# observer.net
KiCad netlist of a schematic drawn in EAGLE
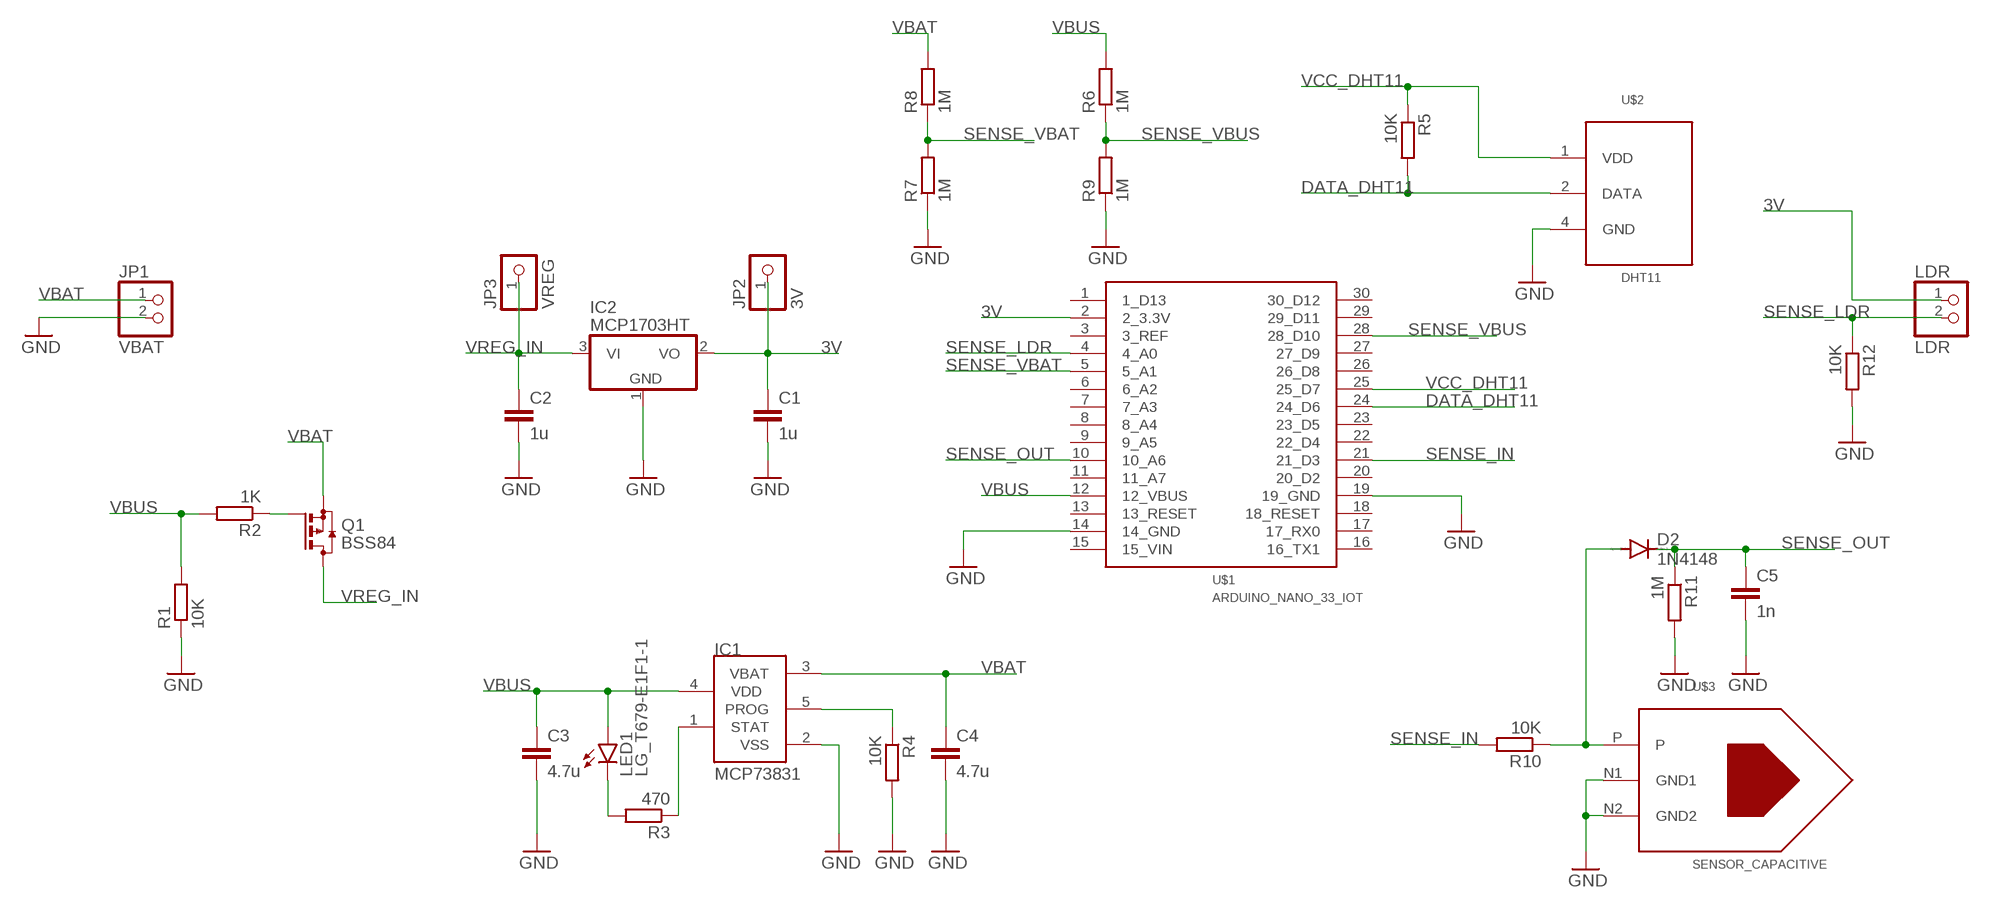
[diagram p0: schematic, sheet 1]

(export (version "E")
  (design (tool "Eeschema 10.0.6"))
  (components
    (comp (ref "C1")
      (value "1u")
      (footprint "eagle-import:C0805")
      (libsource (lib "eagle-import") (part "C-EUC0805"))
    )
    (comp (ref "C2")
      (value "1u")
      (footprint "eagle-import:C0805")
      (libsource (lib "eagle-import") (part "C-EUC0805"))
    )
    (comp (ref "C3")
      (value "4.7u")
      (footprint "eagle-import:C0805")
      (libsource (lib "eagle-import") (part "C-EUC0805"))
    )
    (comp (ref "C4")
      (value "4.7u")
      (footprint "eagle-import:C0805")
      (libsource (lib "eagle-import") (part "C-EUC0805"))
    )
    (comp (ref "C5")
      (value "1n")
      (footprint "eagle-import:C0805")
      (libsource (lib "eagle-import") (part "C-EUC0805"))
    )
    (comp (ref "D2")
      (value "1N4148")
      (footprint "eagle-import:MICROMELF-W")
      (libsource (lib "eagle-import") (part "DIODE-MICROMELF-W"))
    )
    (comp (ref "IC1")
      (value "MCP73831")
      (footprint "eagle-import:SOT23-5L")
      (libsource (lib "eagle-import") (part "MCP73831"))
    )
    (comp (ref "IC2")
      (value "MCP1703HT")
      (footprint "eagle-import:SOT23")
      (libsource (lib "eagle-import") (part "MCP1703CB"))
    )
    (comp (ref "JP1")
      (value "VBAT")
      (footprint "eagle-import:1X02")
      (libsource (lib "eagle-import") (part "PINHD-1X2"))
    )
    (comp (ref "JP2")
      (value "3V")
      (footprint "eagle-import:1X01")
      (libsource (lib "eagle-import") (part "PINHD-1X1"))
    )
    (comp (ref "JP3")
      (value "VREG")
      (footprint "eagle-import:1X01")
      (libsource (lib "eagle-import") (part "PINHD-1X1"))
    )
    (comp (ref "LDR")
      (value "LDR")
      (footprint "eagle-import:1X02")
      (libsource (lib "eagle-import") (part "PINHD-1X2"))
    )
    (comp (ref "LED1")
      (value "LG_T679-E1F1-1")
      (footprint "eagle-import:PLCC2")
      (libsource (lib "eagle-import") (part "_T679-?-1E1F1LG"))
    )
    (comp (ref "Q1")
      (value "BSS84")
      (footprint "eagle-import:SOT23")
      (libsource (lib "eagle-import") (part "BSS84"))
    )
    (comp (ref "R1")
      (value "10K")
      (footprint "eagle-import:R0805")
      (libsource (lib "eagle-import") (part "R-EU_R0805"))
    )
    (comp (ref "R2")
      (value "1K")
      (footprint "eagle-import:R0805")
      (libsource (lib "eagle-import") (part "R-EU_R0805"))
    )
    (comp (ref "R3")
      (value "470")
      (footprint "eagle-import:R0805")
      (libsource (lib "eagle-import") (part "R-EU_R0805"))
    )
    (comp (ref "R4")
      (value "10K")
      (footprint "eagle-import:R0805")
      (libsource (lib "eagle-import") (part "R-EU_R0805"))
    )
    (comp (ref "R5")
      (value "10K")
      (footprint "eagle-import:R0805")
      (libsource (lib "eagle-import") (part "R-EU_R0805"))
    )
    (comp (ref "R6")
      (value "1M")
      (footprint "eagle-import:R0805")
      (libsource (lib "eagle-import") (part "R-EU_R0805"))
    )
    (comp (ref "R7")
      (value "1M")
      (footprint "eagle-import:R0805")
      (libsource (lib "eagle-import") (part "R-EU_R0805"))
    )
    (comp (ref "R8")
      (value "1M")
      (footprint "eagle-import:R0805")
      (libsource (lib "eagle-import") (part "R-EU_R0805"))
    )
    (comp (ref "R9")
      (value "1M")
      (footprint "eagle-import:R0805")
      (libsource (lib "eagle-import") (part "R-EU_R0805"))
    )
    (comp (ref "R10")
      (value "10K")
      (footprint "eagle-import:R0805")
      (libsource (lib "eagle-import") (part "R-EU_R0805"))
    )
    (comp (ref "R11")
      (value "1M")
      (footprint "eagle-import:R0805")
      (libsource (lib "eagle-import") (part "R-EU_R0805"))
    )
    (comp (ref "R12")
      (value "10K")
      (footprint "eagle-import:R0805")
      (libsource (lib "eagle-import") (part "R-EU_R0805"))
    )
    (comp (ref "U$1")
      (value "ARDUINO_NANO_33_IOT")
      (footprint "eagle-import:ARDUINO_NANO_33_IOT")
      (libsource (lib "eagle-import") (part "ARDUINO_NANO_33_IOT"))
    )
    (comp (ref "U$2")
      (value "DHT11")
      (footprint "eagle-import:DHT11")
      (libsource (lib "eagle-import") (part "DHT11"))
    )
    (comp (ref "U$3")
      (value "SENSOR_CAPACITIVE")
      (footprint "eagle-import:SENSOR_CAPACITIVE_MOISTURE")
      (libsource (lib "eagle-import") (part "SENSOR_CAPACITIVE"))
    )
  )
  (nets
    (net (code "1") (name "/3V") (class "Default")
      (node (ref "C1") (pin "1") (pinfunction "1_1") (pintype "passive"))
      (node (ref "IC2") (pin "2") (pinfunction "VO_2") (pintype "passive"))
      (node (ref "JP2") (pin "1") (pinfunction "1_1") (pintype "passive"))
      (node (ref "LDR") (pin "1") (pinfunction "1_1") (pintype "passive"))
      (node (ref "U$1") (pin "2") (pinfunction "2_3.3V_2") (pintype "bidirectional"))
    )
    (net (code "2") (name "/DATA_DHT11") (class "Default")
      (node (ref "R5") (pin "2") (pinfunction "2_2") (pintype "passive"))
      (node (ref "U$1") (pin "24") (pinfunction "24_D6_24") (pintype "bidirectional"))
      (node (ref "U$2") (pin "2") (pinfunction "DATA_2") (pintype "bidirectional"))
    )
    (net (code "3") (name "/SENSE_IN") (class "Default")
      (node (ref "R10") (pin "2") (pinfunction "2_2") (pintype "passive"))
      (node (ref "U$1") (pin "21") (pinfunction "21_D3_21") (pintype "bidirectional"))
    )
    (net (code "4") (name "/SENSE_LDR") (class "Default")
      (node (ref "LDR") (pin "2") (pinfunction "2_2") (pintype "passive"))
      (node (ref "R12") (pin "1") (pinfunction "1_1") (pintype "passive"))
      (node (ref "U$1") (pin "4") (pinfunction "4_A0_4") (pintype "bidirectional"))
    )
    (net (code "5") (name "/SENSE_OUT") (class "Default")
      (node (ref "C5") (pin "1") (pinfunction "1_1") (pintype "passive"))
      (node (ref "D2") (pin "C") (pinfunction "C_C") (pintype "passive"))
      (node (ref "R11") (pin "1") (pinfunction "1_1") (pintype "passive"))
      (node (ref "U$1") (pin "10") (pinfunction "10_A6_10") (pintype "bidirectional"))
    )
    (net (code "6") (name "/SENSE_VBAT") (class "Default")
      (node (ref "R7") (pin "2") (pinfunction "2_2") (pintype "passive"))
      (node (ref "R8") (pin "1") (pinfunction "1_1") (pintype "passive"))
      (node (ref "U$1") (pin "5") (pinfunction "5_A1_5") (pintype "bidirectional"))
    )
    (net (code "7") (name "/SENSE_VBUS") (class "Default")
      (node (ref "R6") (pin "1") (pinfunction "1_1") (pintype "passive"))
      (node (ref "R9") (pin "2") (pinfunction "2_2") (pintype "passive"))
      (node (ref "U$1") (pin "28") (pinfunction "28_D10_28") (pintype "bidirectional"))
    )
    (net (code "8") (name "/VBAT") (class "Default")
      (node (ref "C4") (pin "1") (pinfunction "1_1") (pintype "passive"))
      (node (ref "IC1") (pin "3") (pinfunction "VBAT_3") (pintype "bidirectional"))
      (node (ref "JP1") (pin "1") (pinfunction "1_1") (pintype "passive"))
      (node (ref "Q1") (pin "2") (pinfunction "S_2") (pintype "passive"))
      (node (ref "R8") (pin "2") (pinfunction "2_2") (pintype "passive"))
    )
    (net (code "9") (name "/VBUS") (class "Default")
      (node (ref "C3") (pin "1") (pinfunction "1_1") (pintype "passive"))
      (node (ref "IC1") (pin "4") (pinfunction "VDD_4") (pintype "bidirectional"))
      (node (ref "LED1") (pin "A") (pinfunction "A_A") (pintype "passive"))
      (node (ref "R1") (pin "2") (pinfunction "2_2") (pintype "passive"))
      (node (ref "R2") (pin "2") (pinfunction "2_2") (pintype "passive"))
      (node (ref "R6") (pin "2") (pinfunction "2_2") (pintype "passive"))
      (node (ref "U$1") (pin "12") (pinfunction "12_VBUS_12") (pintype "bidirectional"))
    )
    (net (code "10") (name "/VCC_DHT11") (class "Default")
      (node (ref "R5") (pin "1") (pinfunction "1_1") (pintype "passive"))
      (node (ref "U$1") (pin "25") (pinfunction "25_D7_25") (pintype "bidirectional"))
      (node (ref "U$2") (pin "1") (pinfunction "VDD_1") (pintype "bidirectional"))
    )
    (net (code "11") (name "/VREG_IN") (class "Default")
      (node (ref "C2") (pin "1") (pinfunction "1_1") (pintype "passive"))
      (node (ref "IC2") (pin "3") (pinfunction "VI_3") (pintype "input"))
      (node (ref "JP3") (pin "1") (pinfunction "1_1") (pintype "passive"))
      (node (ref "Q1") (pin "3") (pinfunction "D_3") (pintype "passive"))
    )
    (net (code "12") (name "GND") (class "Default")
      (node (ref "C1") (pin "2") (pinfunction "2_2") (pintype "passive"))
      (node (ref "C2") (pin "2") (pinfunction "2_2") (pintype "passive"))
      (node (ref "C3") (pin "2") (pinfunction "2_2") (pintype "passive"))
      (node (ref "C4") (pin "2") (pinfunction "2_2") (pintype "passive"))
      (node (ref "C5") (pin "2") (pinfunction "2_2") (pintype "passive"))
      (node (ref "IC1") (pin "2") (pinfunction "VSS_2") (pintype "bidirectional"))
      (node (ref "IC2") (pin "1") (pinfunction "GND_1") (pintype "passive"))
      (node (ref "JP1") (pin "2") (pinfunction "2_2") (pintype "passive"))
      (node (ref "R1") (pin "1") (pinfunction "1_1") (pintype "passive"))
      (node (ref "R11") (pin "2") (pinfunction "2_2") (pintype "passive"))
      (node (ref "R12") (pin "2") (pinfunction "2_2") (pintype "passive"))
      (node (ref "R4") (pin "2") (pinfunction "2_2") (pintype "passive"))
      (node (ref "R7") (pin "1") (pinfunction "1_1") (pintype "passive"))
      (node (ref "R9") (pin "1") (pinfunction "1_1") (pintype "passive"))
      (node (ref "U$1") (pin "14") (pinfunction "14_GND_14") (pintype "bidirectional"))
      (node (ref "U$1") (pin "19") (pinfunction "19_GND_19") (pintype "bidirectional"))
      (node (ref "U$2") (pin "4") (pinfunction "GND_4") (pintype "bidirectional"))
      (node (ref "U$3") (pin "N1") (pinfunction "GND1_N1") (pintype "bidirectional"))
      (node (ref "U$3") (pin "N2") (pinfunction "GND2_N2") (pintype "bidirectional"))
    )
    (net (code "13") (name "Net-(D2-PadA)") (class "Default")
      (node (ref "D2") (pin "A") (pinfunction "A_A") (pintype "passive"))
      (node (ref "R10") (pin "1") (pinfunction "1_1") (pintype "passive"))
      (node (ref "U$3") (pin "P") (pinfunction "P_P") (pintype "bidirectional"))
    )
    (net (code "14") (name "Net-(IC1-PROG)") (class "Default")
      (node (ref "IC1") (pin "5") (pinfunction "PROG_5") (pintype "bidirectional"))
      (node (ref "R4") (pin "1") (pinfunction "1_1") (pintype "passive"))
    )
    (net (code "15") (name "Net-(IC1-STAT)") (class "Default")
      (node (ref "IC1") (pin "1") (pinfunction "STAT_1") (pintype "bidirectional"))
      (node (ref "R3") (pin "1") (pinfunction "1_1") (pintype "passive"))
    )
    (net (code "16") (name "Net-(LED1-PadC)") (class "Default")
      (node (ref "LED1") (pin "C") (pinfunction "C_C") (pintype "passive"))
      (node (ref "R3") (pin "2") (pinfunction "2_2") (pintype "passive"))
    )
    (net (code "17") (name "Net-(Q1-G)") (class "Default")
      (node (ref "Q1") (pin "1") (pinfunction "G_1") (pintype "passive"))
      (node (ref "R2") (pin "1") (pinfunction "1_1") (pintype "passive"))
    )
    (net (code "18") (name "unconnected-(U$1-1_D13-Pad1)") (class "Default")
      (node (ref "U$1") (pin "1") (pinfunction "1_D13_1") (pintype "bidirectional"))
    )
    (net (code "19") (name "unconnected-(U$1-3_REF-Pad3)") (class "Default")
      (node (ref "U$1") (pin "3") (pinfunction "3_REF_3") (pintype "bidirectional"))
    )
    (net (code "20") (name "unconnected-(U$1-6_A2-Pad6)") (class "Default")
      (node (ref "U$1") (pin "6") (pinfunction "6_A2_6") (pintype "bidirectional"))
    )
    (net (code "21") (name "unconnected-(U$1-7_A3-Pad7)") (class "Default")
      (node (ref "U$1") (pin "7") (pinfunction "7_A3_7") (pintype "bidirectional"))
    )
    (net (code "22") (name "unconnected-(U$1-8_A4-Pad8)") (class "Default")
      (node (ref "U$1") (pin "8") (pinfunction "8_A4_8") (pintype "bidirectional"))
    )
    (net (code "23") (name "unconnected-(U$1-9_A5-Pad9)") (class "Default")
      (node (ref "U$1") (pin "9") (pinfunction "9_A5_9") (pintype "bidirectional"))
    )
    (net (code "24") (name "unconnected-(U$1-11_A7-Pad11)") (class "Default")
      (node (ref "U$1") (pin "11") (pinfunction "11_A7_11") (pintype "bidirectional"))
    )
    (net (code "25") (name "unconnected-(U$1-13_RESET-Pad13)") (class "Default")
      (node (ref "U$1") (pin "13") (pinfunction "13_RESET_13") (pintype "bidirectional"))
    )
    (net (code "26") (name "unconnected-(U$1-15_VIN-Pad15)") (class "Default")
      (node (ref "U$1") (pin "15") (pinfunction "15_VIN_15") (pintype "bidirectional"))
    )
    (net (code "27") (name "unconnected-(U$1-16_TX1-Pad16)") (class "Default")
      (node (ref "U$1") (pin "16") (pinfunction "16_TX1_16") (pintype "bidirectional"))
    )
    (net (code "28") (name "unconnected-(U$1-17_RX0-Pad17)") (class "Default")
      (node (ref "U$1") (pin "17") (pinfunction "17_RX0_17") (pintype "bidirectional"))
    )
    (net (code "29") (name "unconnected-(U$1-18_RESET-Pad18)") (class "Default")
      (node (ref "U$1") (pin "18") (pinfunction "18_RESET_18") (pintype "bidirectional"))
    )
    (net (code "30") (name "unconnected-(U$1-20_D2-Pad20)") (class "Default")
      (node (ref "U$1") (pin "20") (pinfunction "20_D2_20") (pintype "bidirectional"))
    )
    (net (code "31") (name "unconnected-(U$1-22_D4-Pad22)") (class "Default")
      (node (ref "U$1") (pin "22") (pinfunction "22_D4_22") (pintype "bidirectional"))
    )
    (net (code "32") (name "unconnected-(U$1-23_D5-Pad23)") (class "Default")
      (node (ref "U$1") (pin "23") (pinfunction "23_D5_23") (pintype "bidirectional"))
    )
    (net (code "33") (name "unconnected-(U$1-26_D8-Pad26)") (class "Default")
      (node (ref "U$1") (pin "26") (pinfunction "26_D8_26") (pintype "bidirectional"))
    )
    (net (code "34") (name "unconnected-(U$1-27_D9-Pad27)") (class "Default")
      (node (ref "U$1") (pin "27") (pinfunction "27_D9_27") (pintype "bidirectional"))
    )
    (net (code "35") (name "unconnected-(U$1-29_D11-Pad29)") (class "Default")
      (node (ref "U$1") (pin "29") (pinfunction "29_D11_29") (pintype "bidirectional"))
    )
    (net (code "36") (name "unconnected-(U$1-30_D12-Pad30)") (class "Default")
      (node (ref "U$1") (pin "30") (pinfunction "30_D12_30") (pintype "bidirectional"))
    )
  )
)
